# v2164_quad_VC_mixer_w_ext_in_0402_DIL.net
KiCad netlist of a schematic drawn in EAGLE
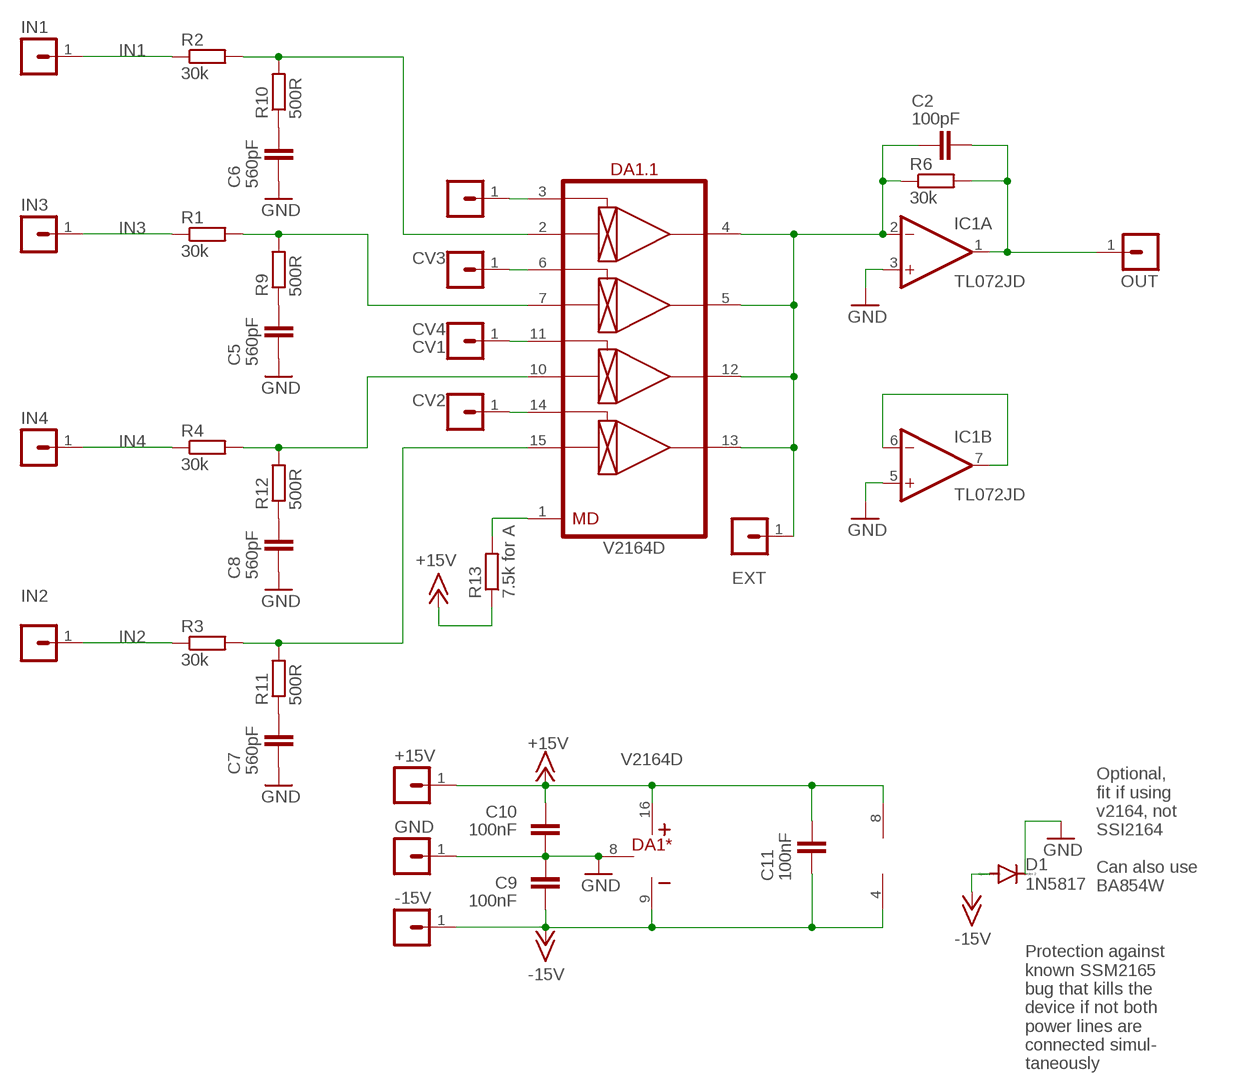
[diagram p0: schematic, sheet 1]

(export (version "E")
  (design (tool "Eeschema 10.0.6"))
  (components
    (comp (ref "+15V")
      (value "MA01-1JP")
      (footprint "eagle-import:SIP-PIN01-1J")
      (libsource (lib "eagle-import") (part "MA01-1JP"))
    )
    (comp (ref "-15V")
      (value "MA01-1JP")
      (footprint "eagle-import:SIP-PIN01-1J")
      (libsource (lib "eagle-import") (part "MA01-1JP"))
    )
    (comp (ref "C2")
      (value "100pF")
      (footprint "eagle-import:C0402")
      (libsource (lib "eagle-import") (part "C-EUC0402"))
    )
    (comp (ref "C5")
      (value "560pF")
      (footprint "eagle-import:C0603")
      (libsource (lib "eagle-import") (part "C-EUC0603"))
    )
    (comp (ref "C6")
      (value "560pF")
      (footprint "eagle-import:C0603")
      (libsource (lib "eagle-import") (part "C-EUC0603"))
    )
    (comp (ref "C7")
      (value "560pF")
      (footprint "eagle-import:C0603")
      (libsource (lib "eagle-import") (part "C-EUC0603"))
    )
    (comp (ref "C8")
      (value "560pF")
      (footprint "eagle-import:C0603")
      (libsource (lib "eagle-import") (part "C-EUC0603"))
    )
    (comp (ref "C9")
      (value "100nF")
      (footprint "eagle-import:C0402")
      (libsource (lib "eagle-import") (part "C-EUC0402"))
    )
    (comp (ref "C10")
      (value "100nF")
      (footprint "eagle-import:C0402")
      (libsource (lib "eagle-import") (part "C-EUC0402"))
    )
    (comp (ref "C11")
      (value "100nF")
      (footprint "eagle-import:C0402")
      (libsource (lib "eagle-import") (part "C-EUC0402"))
    )
    (comp (ref "CV1")
      (value "MA01-1JP")
      (footprint "eagle-import:SIP-PIN01-1J")
      (libsource (lib "eagle-import") (part "MA01-1JP"))
    )
    (comp (ref "CV2")
      (value "MA01-1JP")
      (footprint "eagle-import:SIP-PIN01-1J")
      (libsource (lib "eagle-import") (part "MA01-1JP"))
    )
    (comp (ref "CV3")
      (value "MA01-1JP")
      (footprint "eagle-import:SIP-PIN01-1J")
      (libsource (lib "eagle-import") (part "MA01-1JP"))
    )
    (comp (ref "CV4")
      (value "MA01-1JP")
      (footprint "eagle-import:SIP-PIN01-1J")
      (libsource (lib "eagle-import") (part "MA01-1JP"))
    )
    (comp (ref "D1")
      (value "1N5817")
      (footprint "eagle-import:SOD323-R")
      (libsource (lib "eagle-import") (part "DIODE-SOD323-R"))
    )
    (comp (ref "DA1")
      (value "V2164D")
      (footprint "eagle-import:DIP-16")
      (libsource (lib "eagle-import") (part "V2164D"))
    )
    (comp (ref "EXT")
      (value "MA01-1JP")
      (footprint "eagle-import:SIP-PIN01-1J")
      (libsource (lib "eagle-import") (part "MA01-1JP"))
    )
    (comp (ref "GND")
      (value "MA01-1JP")
      (footprint "eagle-import:SIP-PIN01-1J")
      (libsource (lib "eagle-import") (part "MA01-1JP"))
    )
    (comp (ref "IC1")
      (value "TL072JD")
      (footprint "eagle-import:SO08J")
      (libsource (lib "eagle-import") (part "TL072JD"))
    )
    (comp (ref "IN1")
      (value "MA01-1JP")
      (footprint "eagle-import:SIP-PIN01-1J")
      (libsource (lib "eagle-import") (part "MA01-1JP"))
    )
    (comp (ref "IN2")
      (value "MA01-1JP")
      (footprint "eagle-import:SIP-PIN01-1J")
      (libsource (lib "eagle-import") (part "MA01-1JP"))
    )
    (comp (ref "IN3")
      (value "MA01-1JP")
      (footprint "eagle-import:SIP-PIN01-1J")
      (libsource (lib "eagle-import") (part "MA01-1JP"))
    )
    (comp (ref "IN4")
      (value "MA01-1JP")
      (footprint "eagle-import:SIP-PIN01-1J")
      (libsource (lib "eagle-import") (part "MA01-1JP"))
    )
    (comp (ref "OUT")
      (value "MA01-1JP")
      (footprint "eagle-import:SIP-PIN01-1J")
      (libsource (lib "eagle-import") (part "MA01-1JP"))
    )
    (comp (ref "R1")
      (value "30k")
      (footprint "eagle-import:R0402")
      (libsource (lib "eagle-import") (part "R-EU_R0402"))
    )
    (comp (ref "R2")
      (value "30k")
      (footprint "eagle-import:R0402")
      (libsource (lib "eagle-import") (part "R-EU_R0402"))
    )
    (comp (ref "R3")
      (value "30k")
      (footprint "eagle-import:R0402")
      (libsource (lib "eagle-import") (part "R-EU_R0402"))
    )
    (comp (ref "R4")
      (value "30k")
      (footprint "eagle-import:R0402")
      (libsource (lib "eagle-import") (part "R-EU_R0402"))
    )
    (comp (ref "R6")
      (value "30k")
      (footprint "eagle-import:R0402")
      (libsource (lib "eagle-import") (part "R-EU_R0402"))
    )
    (comp (ref "R9")
      (value "500R")
      (footprint "eagle-import:R0402")
      (libsource (lib "eagle-import") (part "R-EU_R0402"))
    )
    (comp (ref "R10")
      (value "500R")
      (footprint "eagle-import:R0402")
      (libsource (lib "eagle-import") (part "R-EU_R0402"))
    )
    (comp (ref "R11")
      (value "500R")
      (footprint "eagle-import:R0402")
      (libsource (lib "eagle-import") (part "R-EU_R0402"))
    )
    (comp (ref "R12")
      (value "500R")
      (footprint "eagle-import:R0402")
      (libsource (lib "eagle-import") (part "R-EU_R0402"))
    )
    (comp (ref "R13")
      (value "7.5k for A")
      (footprint "eagle-import:R0402")
      (libsource (lib "eagle-import") (part "R-EU_R0402"))
    )
  )
  (nets
    (net (code "1") (name "+15V") (class "Default")
      (node (ref "+15V") (pin "1") (pinfunction "1_1") (pintype "passive"))
      (node (ref "C10") (pin "2") (pinfunction "2_2") (pintype "passive"))
      (node (ref "C11") (pin "2") (pinfunction "2_2") (pintype "passive"))
      (node (ref "DA1") (pin "16") (pinfunction "V+_16") (pintype "power_in"))
      (node (ref "IC1") (pin "8") (pinfunction "V+_8") (pintype "power_in"))
      (node (ref "R13") (pin "1") (pinfunction "1_1") (pintype "passive"))
    )
    (net (code "2") (name "-15V") (class "Default")
      (node (ref "-15V") (pin "1") (pinfunction "1_1") (pintype "passive"))
      (node (ref "C11") (pin "1") (pinfunction "1_1") (pintype "passive"))
      (node (ref "C9") (pin "1") (pinfunction "1_1") (pintype "passive"))
      (node (ref "D1") (pin "A") (pinfunction "A_A") (pintype "passive"))
      (node (ref "DA1") (pin "9") (pinfunction "V-_9") (pintype "power_in"))
      (node (ref "IC1") (pin "4") (pinfunction "V-_4") (pintype "power_in"))
    )
    (net (code "3") (name "/IN1") (class "Default")
      (node (ref "IN1") (pin "1") (pinfunction "1_1") (pintype "passive"))
      (node (ref "R2") (pin "1") (pinfunction "1_1") (pintype "passive"))
    )
    (net (code "4") (name "/IN2") (class "Default")
      (node (ref "IN2") (pin "1") (pinfunction "1_1") (pintype "passive"))
      (node (ref "R3") (pin "1") (pinfunction "1_1") (pintype "passive"))
    )
    (net (code "5") (name "/IN3") (class "Default")
      (node (ref "IN3") (pin "1") (pinfunction "1_1") (pintype "passive"))
      (node (ref "R1") (pin "1") (pinfunction "1_1") (pintype "passive"))
    )
    (net (code "6") (name "/IN4") (class "Default")
      (node (ref "IN4") (pin "1") (pinfunction "1_1") (pintype "passive"))
      (node (ref "R4") (pin "1") (pinfunction "1_1") (pintype "passive"))
    )
    (net (code "7") (name "GND") (class "Default")
      (node (ref "C10") (pin "1") (pinfunction "1_1") (pintype "passive"))
      (node (ref "C5") (pin "1") (pinfunction "1_1") (pintype "passive"))
      (node (ref "C6") (pin "1") (pinfunction "1_1") (pintype "passive"))
      (node (ref "C7") (pin "1") (pinfunction "1_1") (pintype "passive"))
      (node (ref "C8") (pin "1") (pinfunction "1_1") (pintype "passive"))
      (node (ref "C9") (pin "2") (pinfunction "2_2") (pintype "passive"))
      (node (ref "D1") (pin "C") (pinfunction "C_C") (pintype "passive"))
      (node (ref "DA1") (pin "8") (pinfunction "GND_8") (pintype "power_in"))
      (node (ref "GND") (pin "1") (pinfunction "1_1") (pintype "passive"))
      (node (ref "IC1") (pin "3") (pinfunction "+IN_3") (pintype "input"))
      (node (ref "IC1") (pin "5") (pinfunction "+IN_5") (pintype "input"))
    )
    (net (code "8") (name "Net-(C5-Pad2)") (class "Default")
      (node (ref "C5") (pin "2") (pinfunction "2_2") (pintype "passive"))
      (node (ref "R9") (pin "1") (pinfunction "1_1") (pintype "passive"))
    )
    (net (code "9") (name "Net-(C6-Pad2)") (class "Default")
      (node (ref "C6") (pin "2") (pinfunction "2_2") (pintype "passive"))
      (node (ref "R10") (pin "1") (pinfunction "1_1") (pintype "passive"))
    )
    (net (code "10") (name "Net-(C7-Pad2)") (class "Default")
      (node (ref "C7") (pin "2") (pinfunction "2_2") (pintype "passive"))
      (node (ref "R11") (pin "1") (pinfunction "1_1") (pintype "passive"))
    )
    (net (code "11") (name "Net-(C8-Pad2)") (class "Default")
      (node (ref "C8") (pin "2") (pinfunction "2_2") (pintype "passive"))
      (node (ref "R12") (pin "1") (pinfunction "1_1") (pintype "passive"))
    )
    (net (code "12") (name "Net-(DA1B-CV1)") (class "Default")
      (node (ref "CV1") (pin "1") (pinfunction "1_1") (pintype "passive"))
      (node (ref "DA1") (pin "3") (pinfunction "CV1_3") (pintype "input"))
    )
    (net (code "13") (name "Net-(DA1B-CV2)") (class "Default")
      (node (ref "CV3") (pin "1") (pinfunction "1_1") (pintype "passive"))
      (node (ref "DA1") (pin "6") (pinfunction "CV2_6") (pintype "input"))
    )
    (net (code "14") (name "Net-(DA1B-CV3)") (class "Default")
      (node (ref "CV4") (pin "1") (pinfunction "1_1") (pintype "passive"))
      (node (ref "DA1") (pin "11") (pinfunction "CV3_11") (pintype "input"))
    )
    (net (code "15") (name "Net-(DA1B-CV4)") (class "Default")
      (node (ref "CV2") (pin "1") (pinfunction "1_1") (pintype "passive"))
      (node (ref "DA1") (pin "14") (pinfunction "CV4_14") (pintype "input"))
    )
    (net (code "16") (name "Net-(DA1B-IN1)") (class "Default")
      (node (ref "DA1") (pin "2") (pinfunction "IN1_2") (pintype "input"))
      (node (ref "R10") (pin "2") (pinfunction "2_2") (pintype "passive"))
      (node (ref "R2") (pin "2") (pinfunction "2_2") (pintype "passive"))
    )
    (net (code "17") (name "Net-(DA1B-IN2)") (class "Default")
      (node (ref "DA1") (pin "7") (pinfunction "IN2_7") (pintype "input"))
      (node (ref "R1") (pin "2") (pinfunction "2_2") (pintype "passive"))
      (node (ref "R9") (pin "2") (pinfunction "2_2") (pintype "passive"))
    )
    (net (code "18") (name "Net-(DA1B-IN3)") (class "Default")
      (node (ref "DA1") (pin "10") (pinfunction "IN3_10") (pintype "input"))
      (node (ref "R12") (pin "2") (pinfunction "2_2") (pintype "passive"))
      (node (ref "R4") (pin "2") (pinfunction "2_2") (pintype "passive"))
    )
    (net (code "19") (name "Net-(DA1B-IN4)") (class "Default")
      (node (ref "DA1") (pin "15") (pinfunction "IN4_15") (pintype "input"))
      (node (ref "R11") (pin "2") (pinfunction "2_2") (pintype "passive"))
      (node (ref "R3") (pin "2") (pinfunction "2_2") (pintype "passive"))
    )
    (net (code "20") (name "Net-(DA1B-MD)") (class "Default")
      (node (ref "DA1") (pin "1") (pinfunction "MD_1") (pintype "output"))
      (node (ref "R13") (pin "2") (pinfunction "2_2") (pintype "passive"))
    )
    (net (code "21") (name "Net-(DA1B-OUT1)") (class "Default")
      (node (ref "C2") (pin "1") (pinfunction "1_1") (pintype "passive"))
      (node (ref "DA1") (pin "12") (pinfunction "OUT3_12") (pintype "output"))
      (node (ref "DA1") (pin "13") (pinfunction "OUT4_13") (pintype "output"))
      (node (ref "DA1") (pin "4") (pinfunction "OUT1_4") (pintype "output"))
      (node (ref "DA1") (pin "5") (pinfunction "OUT2_5") (pintype "output"))
      (node (ref "EXT") (pin "1") (pinfunction "1_1") (pintype "passive"))
      (node (ref "IC1") (pin "2") (pinfunction "-IN_2") (pintype "input"))
      (node (ref "R6") (pin "1") (pinfunction "1_1") (pintype "passive"))
    )
    (net (code "22") (name "Net-(IC1A-OUT)") (class "Default")
      (node (ref "C2") (pin "2") (pinfunction "2_2") (pintype "passive"))
      (node (ref "IC1") (pin "1") (pinfunction "OUT_1") (pintype "output"))
      (node (ref "OUT") (pin "1") (pinfunction "1_1") (pintype "passive"))
      (node (ref "R6") (pin "2") (pinfunction "2_2") (pintype "passive"))
    )
    (net (code "23") (name "Net-(IC1B--IN)") (class "Default")
      (node (ref "IC1") (pin "6") (pinfunction "-IN_6") (pintype "input"))
      (node (ref "IC1") (pin "7") (pinfunction "OUT_7") (pintype "output"))
    )
  )
)
